# SPIDERnew.net
KiCad netlist of a schematic drawn in EAGLE
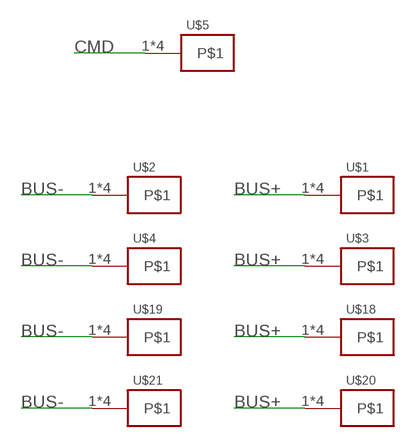
[diagram p0: schematic, sheet 1]

(export (version "E")
  (design (tool "Eeschema 10.0.6"))
  (components
    (comp (ref "U$1")
      (value "KCONNECT-")
      (footprint "eagle-import:KCONNECT-")
      (libsource (lib "eagle-import") (part "KCONNECT-"))
    )
    (comp (ref "U$2")
      (value "KCONNECT-")
      (footprint "eagle-import:KCONNECT-")
      (libsource (lib "eagle-import") (part "KCONNECT-"))
    )
    (comp (ref "U$3")
      (value "KCONNECT-")
      (footprint "eagle-import:KCONNECT-")
      (libsource (lib "eagle-import") (part "KCONNECT-"))
    )
    (comp (ref "U$4")
      (value "KCONNECT-")
      (footprint "eagle-import:KCONNECT-")
      (libsource (lib "eagle-import") (part "KCONNECT-"))
    )
    (comp (ref "U$5")
      (value "KCONNECTQUAD-")
      (footprint "eagle-import:KCONNECT-_QUAD")
      (libsource (lib "eagle-import") (part "KCONNECTQUAD-"))
    )
    (comp (ref "U$18")
      (value "KCONNECT-")
      (footprint "eagle-import:KCONNECT-")
      (libsource (lib "eagle-import") (part "KCONNECT-"))
    )
    (comp (ref "U$19")
      (value "KCONNECT-")
      (footprint "eagle-import:KCONNECT-")
      (libsource (lib "eagle-import") (part "KCONNECT-"))
    )
    (comp (ref "U$20")
      (value "KCONNECT-")
      (footprint "eagle-import:KCONNECT-")
      (libsource (lib "eagle-import") (part "KCONNECT-"))
    )
    (comp (ref "U$21")
      (value "KCONNECT-")
      (footprint "eagle-import:KCONNECT-")
      (libsource (lib "eagle-import") (part "KCONNECT-"))
    )
  )
  (nets
    (net (code "1") (name "/BUS+") (class "Default")
      (node (ref "U$1") (pin "1") (pinfunction "P$1_1") (pintype "bidirectional"))
      (node (ref "U$1") (pin "2") (pinfunction "P$1_2") (pintype "bidirectional"))
      (node (ref "U$1") (pin "3") (pinfunction "P$1_3") (pintype "bidirectional"))
      (node (ref "U$1") (pin "4") (pinfunction "P$1_4") (pintype "bidirectional"))
      (node (ref "U$18") (pin "1") (pinfunction "P$1_1") (pintype "bidirectional"))
      (node (ref "U$18") (pin "2") (pinfunction "P$1_2") (pintype "bidirectional"))
      (node (ref "U$18") (pin "3") (pinfunction "P$1_3") (pintype "bidirectional"))
      (node (ref "U$18") (pin "4") (pinfunction "P$1_4") (pintype "bidirectional"))
      (node (ref "U$20") (pin "1") (pinfunction "P$1_1") (pintype "bidirectional"))
      (node (ref "U$20") (pin "2") (pinfunction "P$1_2") (pintype "bidirectional"))
      (node (ref "U$20") (pin "3") (pinfunction "P$1_3") (pintype "bidirectional"))
      (node (ref "U$20") (pin "4") (pinfunction "P$1_4") (pintype "bidirectional"))
      (node (ref "U$3") (pin "1") (pinfunction "P$1_1") (pintype "bidirectional"))
      (node (ref "U$3") (pin "2") (pinfunction "P$1_2") (pintype "bidirectional"))
      (node (ref "U$3") (pin "3") (pinfunction "P$1_3") (pintype "bidirectional"))
      (node (ref "U$3") (pin "4") (pinfunction "P$1_4") (pintype "bidirectional"))
    )
    (net (code "2") (name "/BUS-") (class "Default")
      (node (ref "U$19") (pin "1") (pinfunction "P$1_1") (pintype "bidirectional"))
      (node (ref "U$19") (pin "2") (pinfunction "P$1_2") (pintype "bidirectional"))
      (node (ref "U$19") (pin "3") (pinfunction "P$1_3") (pintype "bidirectional"))
      (node (ref "U$19") (pin "4") (pinfunction "P$1_4") (pintype "bidirectional"))
      (node (ref "U$2") (pin "1") (pinfunction "P$1_1") (pintype "bidirectional"))
      (node (ref "U$2") (pin "2") (pinfunction "P$1_2") (pintype "bidirectional"))
      (node (ref "U$2") (pin "3") (pinfunction "P$1_3") (pintype "bidirectional"))
      (node (ref "U$2") (pin "4") (pinfunction "P$1_4") (pintype "bidirectional"))
      (node (ref "U$21") (pin "1") (pinfunction "P$1_1") (pintype "bidirectional"))
      (node (ref "U$21") (pin "2") (pinfunction "P$1_2") (pintype "bidirectional"))
      (node (ref "U$21") (pin "3") (pinfunction "P$1_3") (pintype "bidirectional"))
      (node (ref "U$21") (pin "4") (pinfunction "P$1_4") (pintype "bidirectional"))
      (node (ref "U$4") (pin "1") (pinfunction "P$1_1") (pintype "bidirectional"))
      (node (ref "U$4") (pin "2") (pinfunction "P$1_2") (pintype "bidirectional"))
      (node (ref "U$4") (pin "3") (pinfunction "P$1_3") (pintype "bidirectional"))
      (node (ref "U$4") (pin "4") (pinfunction "P$1_4") (pintype "bidirectional"))
    )
    (net (code "3") (name "/CMD") (class "Default")
      (node (ref "U$5") (pin "1") (pinfunction "P$1_1") (pintype "bidirectional"))
      (node (ref "U$5") (pin "2") (pinfunction "P$1_2") (pintype "bidirectional"))
      (node (ref "U$5") (pin "3") (pinfunction "P$1_3") (pintype "bidirectional"))
      (node (ref "U$5") (pin "4") (pinfunction "P$1_4") (pintype "bidirectional"))
    )
  )
)
